# ADC_channel.net
KiCad netlist of a schematic drawn in Altium Designer
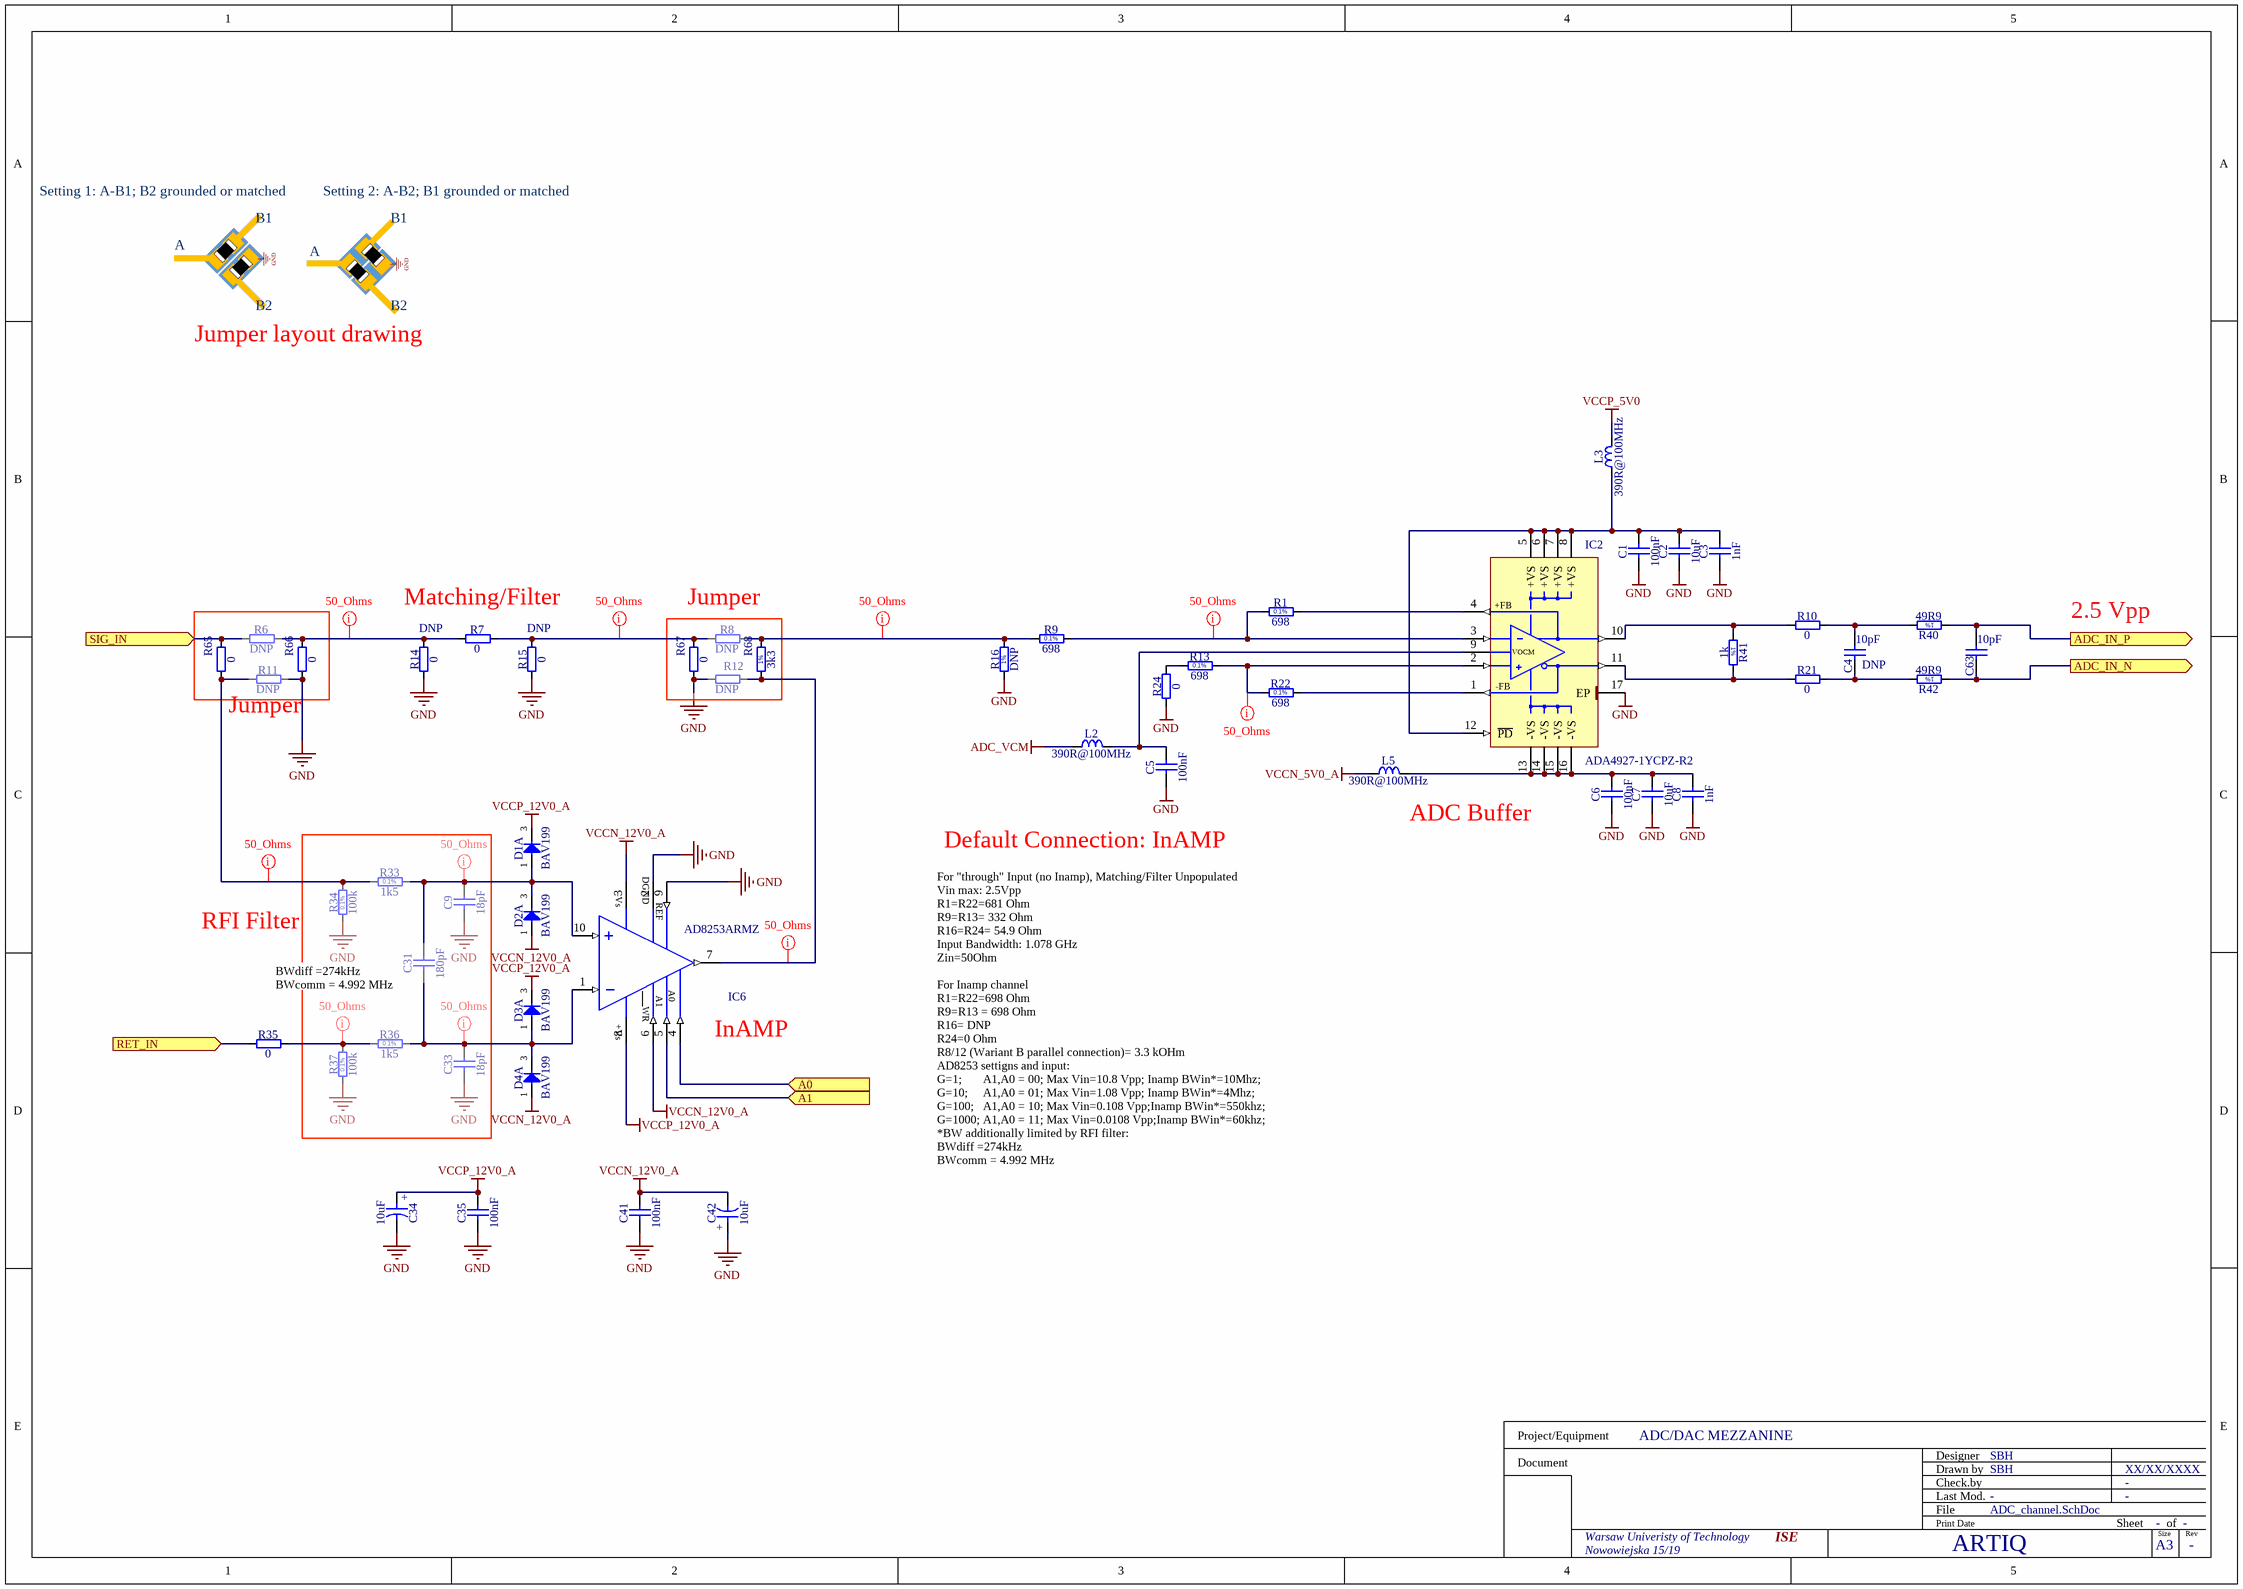
[diagram p0: ADC_channel.SchDoc]

(export (version "E")
  (design (tool "Eeschema 10.0.6"))
  (components
    (comp (ref "C1")
      (value "100nF")
      (footprint "CAPC1005X55N")
      (description "Non-polarised capacitor")
      (fields
        (field (name "PART NUMBER") "CC0402_100NF_16V_10%_X5R")
        (field (name "VOLTAGE") "16V")
        (field (name "AUTHOR") "CERN DEM JLC")
      )
      (libsource (lib "Capacitors") (part "Capacitor - non polarized"))
    )
    (comp (ref "C2")
      (value "10uF")
      (footprint "CAPC1608X87N")
      (description "Non-polarised capacitor")
      (fields
        (field (name "PART NUMBER") "CC0603_10UF_6.3V_20%_X5R")
        (field (name "VOLTAGE") "6.3V")
        (field (name "AUTHOR") "CERN DEM JLC")
      )
      (libsource (lib "Capacitors") (part "Capacitor - non polarized"))
    )
    (comp (ref "C3")
      (value "1nF")
      (footprint "CAPC1005X55N")
      (description "Non-polarised capacitor")
      (fields
        (field (name "PART NUMBER") "CC0402_1NF_50V_10%_X7R")
        (field (name "VOLTAGE") "50V")
        (field (name "AUTHOR") "CERN DEM JLC")
      )
      (libsource (lib "Capacitors") (part "Capacitor - non polarized"))
    )
    (comp (ref "C4")
      (value "10pF")
      (footprint "CAPC1608X87N")
      (description "Non-polarised capacitor")
      (fields
        (field (name "PART NUMBER") "CC0603_10PF_50V_5%_NP0")
        (field (name "VOLTAGE") "50V")
        (field (name "MOUNTED") "DNP")
        (field (name "AUTHOR") "CERN DEM JLC")
      )
      (libsource (lib "Capacitors") (part "Capacitor - non polarized"))
    )
    (comp (ref "C5")
      (value "100nF")
      (footprint "CAPC1005X55N")
      (description "Non-polarised capacitor")
      (fields
        (field (name "PART NUMBER") "CC0402_100NF_16V_10%_X5R")
        (field (name "VOLTAGE") "16V")
        (field (name "AUTHOR") "CERN DEM JLC")
      )
      (libsource (lib "Capacitors") (part "Capacitor - non polarized"))
    )
    (comp (ref "C6")
      (value "100nF")
      (footprint "CAPC1005X55N")
      (description "Non-polarised capacitor")
      (fields
        (field (name "PART NUMBER") "CC0402_100NF_16V_10%_X5R")
        (field (name "VOLTAGE") "16V")
        (field (name "AUTHOR") "CERN DEM JLC")
      )
      (libsource (lib "Capacitors") (part "Capacitor - non polarized"))
    )
    (comp (ref "C7")
      (value "10uF")
      (footprint "CAPC1608X87N")
      (description "Non-polarised capacitor")
      (fields
        (field (name "PART NUMBER") "CC0603_10UF_6.3V_20%_X5R")
        (field (name "VOLTAGE") "6.3V")
        (field (name "AUTHOR") "CERN DEM JLC")
      )
      (libsource (lib "Capacitors") (part "Capacitor - non polarized"))
    )
    (comp (ref "C8")
      (value "1nF")
      (footprint "CAPC1005X55N")
      (description "Non-polarised capacitor")
      (fields
        (field (name "PART NUMBER") "CC0402_1NF_50V_10%_X7R")
        (field (name "VOLTAGE") "50V")
        (field (name "AUTHOR") "CERN DEM JLC")
      )
      (libsource (lib "Capacitors") (part "Capacitor - non polarized"))
    )
    (comp (ref "C9")
      (value "18pF")
      (footprint "CAPC1005X55N")
      (description "Non-polarised capacitor")
      (fields
        (field (name "PART NUMBER") "CC0402_18PF_50V_5%_C0G")
        (field (name "VOLTAGE") "50V")
        (field (name "AUTHOR") "CERN DEM JLC")
      )
      (libsource (lib "Capacitors") (part "Capacitor - non polarized"))
    )
    (comp (ref "C31")
      (value "180pF")
      (footprint "CAPC3216X140N")
      (description "Non-polarised capacitor")
      (fields
        (field (name "PART NUMBER") "CC1206_180PF_50V_5%_NP0")
        (field (name "VOLTAGE") "50V")
        (field (name "AUTHOR") "CERN DEM JLC")
      )
      (libsource (lib "Capacitors") (part "Capacitor - non polarized"))
    )
    (comp (ref "C33")
      (value "18pF")
      (footprint "CAPC1005X55N")
      (description "Non-polarised capacitor")
      (fields
        (field (name "PART NUMBER") "CC0402_18PF_50V_5%_C0G")
        (field (name "VOLTAGE") "50V")
        (field (name "AUTHOR") "CERN DEM JLC")
      )
      (libsource (lib "Capacitors") (part "Capacitor - non polarized"))
    )
    (comp (ref "C34")
      (value "10uF")
      (footprint "CAPMP3216X180N")
      (description "Polarised capacitor")
      (fields
        (field (name "PART NUMBER") "CTE3216-18_10UF_16V_20%_AVX_TCJ")
        (field (name "VOLTAGE") "16V")
        (field (name "AUTHOR") "CERN DEM JLC")
      )
      (libsource (lib "Capacitors") (part "Capacitor - polarized"))
    )
    (comp (ref "C35")
      (value "100nF")
      (footprint "CAPC1005X55N")
      (description "Non-polarised capacitor")
      (fields
        (field (name "PART NUMBER") "CC0402_100NF_16V_10%_X7R")
        (field (name "VOLTAGE") "16V")
        (field (name "AUTHOR") "CERN DEM JLC")
      )
      (libsource (lib "Capacitors") (part "Capacitor - non polarized"))
    )
    (comp (ref "C41")
      (value "100nF")
      (footprint "CAPC1005X55N")
      (description "Non-polarised capacitor")
      (fields
        (field (name "PART NUMBER") "CC0402_100NF_16V_10%_X7R")
        (field (name "VOLTAGE") "16V")
        (field (name "AUTHOR") "CERN DEM JLC")
      )
      (libsource (lib "Capacitors") (part "Capacitor - non polarized"))
    )
    (comp (ref "C42")
      (value "10uF")
      (footprint "CAPMP3216X180N")
      (description "Polarised capacitor")
      (fields
        (field (name "PART NUMBER") "CTE3216-18_10UF_16V_20%_AVX_TCJ")
        (field (name "VOLTAGE") "16V")
        (field (name "AUTHOR") "CERN DEM JLC")
      )
      (libsource (lib "Capacitors") (part "Capacitor - polarized"))
    )
    (comp (ref "C63")
      (value "10pF")
      (footprint "CAPC1608X87N")
      (description "Non-polarised capacitor")
      (fields
        (field (name "PART NUMBER") "CC0603_10PF_50V_5%_NP0")
        (field (name "VOLTAGE") "50V")
        (field (name "AUTHOR") "CERN DEM JLC")
      )
      (libsource (lib "Capacitors") (part "Capacitor - non polarized"))
    )
    (comp (ref "D1")
      (value "BAV199")
      (footprint "SOT95P240X110-3N")
      (description "Serial Diode")
      (fields
        (field (name "VOLTAGE") "75V")
        (field (name "POWER") "250mW")
        (field (name "AUTHOR") "CERN DEM JMW")
      )
      (libsource (lib "ICs And Semiconductors") (part "Diode x2 A1C3_A3C2"))
    )
    (comp (ref "D2")
      (value "BAV199")
      (footprint "SOT95P240X110-3N")
      (description "Serial Diode")
      (fields
        (field (name "VOLTAGE") "75V")
        (field (name "POWER") "250mW")
        (field (name "AUTHOR") "CERN DEM JMW")
      )
      (libsource (lib "ICs And Semiconductors") (part "Diode x2 A1C3_A3C2"))
    )
    (comp (ref "D3")
      (value "BAV199")
      (footprint "SOT95P240X110-3N")
      (description "Serial Diode")
      (fields
        (field (name "VOLTAGE") "75V")
        (field (name "POWER") "250mW")
        (field (name "AUTHOR") "CERN DEM JMW")
      )
      (libsource (lib "ICs And Semiconductors") (part "Diode x2 A1C3_A3C2"))
    )
    (comp (ref "D4")
      (value "BAV199")
      (footprint "SOT95P240X110-3N")
      (description "Serial Diode")
      (fields
        (field (name "VOLTAGE") "75V")
        (field (name "POWER") "250mW")
        (field (name "AUTHOR") "CERN DEM JMW")
      )
      (libsource (lib "ICs And Semiconductors") (part "Diode x2 A1C3_A3C2"))
    )
    (comp (ref "IC2")
      (value "ADA4927-1YCPZ-R2")
      (footprint "QFN50P300X300X100-17N-S145")
      (description "Ultralow Distortion Current Feedback Differential ADC Driver")
      (fields (field (name "MANUFACTURER") "ANALOG DEVICES") (field (name "AUTHOR") "CERN DEM JLC"))
      (libsource (lib "ICs And Semiconductors") (part "ADA4927-1"))
    )
    (comp (ref "IC6")
      (value "AD8253ARMZ")
      (footprint "SOP50P490X110-10N")
      (description "10MHz, 20V/us, G= 1, 10, 100, 1000 iCMOS Programmable Gain Instrumentation Amplifier")
      (fields (field (name "MANUFACTURER") "ANALOG DEVICES") (field (name "AUTHOR") "CERN DEM JLC"))
      (libsource (lib "ICs And Semiconductors") (part "AD8253"))
    )
    (comp (ref "L2")
      (value "390R@100MHz")
      (footprint "INDC1608X95N")
      (description "Inductor")
      (fields
        (field (name "PART NUMBER") "IND0603_TDK_MPZ1608R391A")
        (field (name "POWER") "1.2A")
        (field (name "AUTHOR") "CERN DEM JLC")
      )
      (libsource (lib "Inductors & Transformers") (part "Inductor"))
    )
    (comp (ref "L3")
      (value "390R@100MHz")
      (footprint "INDC1608X95N")
      (description "Inductor")
      (fields
        (field (name "PART NUMBER") "IND0603_TDK_MPZ1608R391A")
        (field (name "POWER") "1.2A")
        (field (name "AUTHOR") "CERN DEM JLC")
      )
      (libsource (lib "") (part "Inductor_1"))
    )
    (comp (ref "L5")
      (value "390R@100MHz")
      (footprint "INDC1608X95N")
      (description "Inductor")
      (fields
        (field (name "PART NUMBER") "IND0603_TDK_MPZ1608R391A")
        (field (name "POWER") "1.2A")
        (field (name "AUTHOR") "CERN DEM JLC")
      )
      (libsource (lib "Inductors & Transformers") (part "Inductor"))
    )
    (comp (ref "R1")
      (value "698")
      (footprint "RESC1608X55N")
      (description "Resistor - 0.1%")
      (fields
        (field (name "PART NUMBER") "R0603_698R_0.1%_0.063W_10PPM")
        (field (name "POWER") "0.063W")
        (field (name "AUTHOR") "CERN DEM JLC")
      )
      (libsource (lib "Resistors") (part "Resistor - 0.1%"))
    )
    (comp (ref "R6")
      (value "DNP")
      (footprint "RESC1005X40N")
      (description "Resistor")
      (fields
        (field (name "PART NUMBER") "R0402_0R_JUMPER")
        (field (name "MANUFACTURER") "GENERIC")
        (field (name "AUTHOR") "CERN DEM JLC")
      )
      (libsource (lib "Resistors") (part "Resistor"))
    )
    (comp (ref "R7")
      (value "0")
      (footprint "RESC1005X40N")
      (description "Resistor")
      (fields
        (field (name "PART NUMBER") "R0402_0R_JUMPER")
        (field (name "MANUFACTURER") "GENERIC")
        (field (name "AUTHOR") "CERN DEM JLC")
      )
      (libsource (lib "Resistors") (part "Resistor"))
    )
    (comp (ref "R8")
      (value "DNP")
      (footprint "RESC1005X40N")
      (description "Resistor")
      (fields
        (field (name "PART NUMBER") "R0402_0R_JUMPER")
        (field (name "MANUFACTURER") "GENERIC")
        (field (name "AUTHOR") "CERN DEM JLC")
      )
      (libsource (lib "Resistors") (part "Resistor"))
    )
    (comp (ref "R9")
      (value "698")
      (footprint "RESC1608X55N")
      (description "Resistor - 0.1%")
      (fields
        (field (name "PART NUMBER") "R0603_698R_0.1%_0.063W_10PPM")
        (field (name "POWER") "0.063W")
        (field (name "AUTHOR") "CERN DEM JLC")
      )
      (libsource (lib "Resistors") (part "Resistor - 0.1%"))
    )
    (comp (ref "R10")
      (value "0")
      (footprint "RESC1005X40N")
      (description "Resistor")
      (fields
        (field (name "PART NUMBER") "R0402_0R_JUMPER")
        (field (name "MANUFACTURER") "GENERIC")
        (field (name "AUTHOR") "CERN DEM JLC")
      )
      (libsource (lib "Resistors") (part "Resistor"))
    )
    (comp (ref "R11")
      (value "DNP")
      (footprint "RESC1005X40N")
      (description "Resistor")
      (fields
        (field (name "PART NUMBER") "R0402_0R_JUMPER")
        (field (name "MANUFACTURER") "GENERIC")
        (field (name "AUTHOR") "CERN DEM JLC")
      )
      (libsource (lib "Resistors") (part "Resistor"))
    )
    (comp (ref "R12")
      (value "DNP")
      (footprint "RESC1005X40N")
      (description "Resistor")
      (fields
        (field (name "PART NUMBER") "R0402_0R_JUMPER")
        (field (name "MANUFACTURER") "GENERIC")
        (field (name "AUTHOR") "CERN DEM JLC")
      )
      (libsource (lib "Resistors") (part "Resistor"))
    )
    (comp (ref "R13")
      (value "698")
      (footprint "RESC1608X55N")
      (description "Resistor - 0.1%")
      (fields
        (field (name "PART NUMBER") "R0603_698R_0.1%_0.063W_10PPM")
        (field (name "POWER") "0.063W")
        (field (name "AUTHOR") "CERN DEM JLC")
      )
      (libsource (lib "Resistors") (part "Resistor - 0.1%"))
    )
    (comp (ref "R14")
      (value "0")
      (footprint "RESC1005X40N")
      (description "Resistor")
      (fields
        (field (name "PART NUMBER") "R0402_0R_JUMPER")
        (field (name "MANUFACTURER") "GENERIC")
        (field (name "MOUNTED") "DNP")
        (field (name "AUTHOR") "CERN DEM JLC")
      )
      (libsource (lib "Resistors") (part "Resistor"))
    )
    (comp (ref "R15")
      (value "0")
      (footprint "RESC1005X40N")
      (description "Resistor")
      (fields
        (field (name "PART NUMBER") "R0402_0R_JUMPER")
        (field (name "MANUFACTURER") "GENERIC")
        (field (name "MOUNTED") "DNP")
        (field (name "AUTHOR") "CERN DEM JLC")
      )
      (libsource (lib "Resistors") (part "Resistor"))
    )
    (comp (ref "R16")
      (value "DNP")
      (footprint "RESC1005X40N")
      (description "Resistor - 1%")
      (fields
        (field (name "PART NUMBER") "R0402_56R_1%_0.0625W_100PPM")
        (field (name "POWER") "0.0625W")
        (field (name "AUTHOR") "CERN DEM JLC")
      )
      (libsource (lib "Resistors") (part "Resistor - 1%"))
    )
    (comp (ref "R21")
      (value "0")
      (footprint "RESC1005X40N")
      (description "Resistor")
      (fields
        (field (name "PART NUMBER") "R0402_0R_JUMPER")
        (field (name "MANUFACTURER") "GENERIC")
        (field (name "AUTHOR") "CERN DEM JLC")
      )
      (libsource (lib "Resistors") (part "Resistor"))
    )
    (comp (ref "R22")
      (value "698")
      (footprint "RESC1608X55N")
      (description "Resistor - 0.1%")
      (fields
        (field (name "PART NUMBER") "R0603_698R_0.1%_0.063W_10PPM")
        (field (name "POWER") "0.063W")
        (field (name "AUTHOR") "CERN DEM JLC")
      )
      (libsource (lib "Resistors") (part "Resistor - 0.1%"))
    )
    (comp (ref "R24")
      (value "0")
      (footprint "RESC1005X40N")
      (description "Resistor")
      (fields
        (field (name "PART NUMBER") "R0402_0R_JUMPER")
        (field (name "MANUFACTURER") "GENERIC")
        (field (name "AUTHOR") "CERN DEM JLC")
      )
      (libsource (lib "Resistors") (part "Resistor"))
    )
    (comp (ref "R33")
      (value "1k5")
      (footprint "RESC1608X55N")
      (description "Resistor - 0.1%")
      (fields
        (field (name "PART NUMBER") "R0603_1K5_0.1%_0.063W_10PPM")
        (field (name "POWER") "0.063W")
        (field (name "AUTHOR") "CERN DEM JLC")
      )
      (libsource (lib "Resistors") (part "Resistor - 0.1%"))
    )
    (comp (ref "R34")
      (value "100k")
      (footprint "RESC1005X35N")
      (description "Resistor - 0.1%")
      (fields
        (field (name "PART NUMBER") "R0402_100K_0.1%_0.063W_25PPM")
        (field (name "POWER") "0.063W")
        (field (name "AUTHOR") "CERN DEM JMW")
      )
      (libsource (lib "Resistors") (part "Resistor - 0.1%"))
    )
    (comp (ref "R35")
      (value "0")
      (footprint "RESC1005X40N")
      (description "Resistor")
      (fields
        (field (name "PART NUMBER") "R0402_0R_JUMPER")
        (field (name "MANUFACTURER") "GENERIC")
        (field (name "AUTHOR") "CERN DEM JLC")
      )
      (libsource (lib "Resistors") (part "Resistor"))
    )
    (comp (ref "R36")
      (value "1k5")
      (footprint "RESC1608X55N")
      (description "Resistor - 0.1%")
      (fields
        (field (name "PART NUMBER") "R0603_1K5_0.1%_0.063W_10PPM")
        (field (name "POWER") "0.063W")
        (field (name "AUTHOR") "CERN DEM JLC")
      )
      (libsource (lib "Resistors") (part "Resistor - 0.1%"))
    )
    (comp (ref "R37")
      (value "100k")
      (footprint "RESC1005X35N")
      (description "Resistor - 0.1%")
      (fields
        (field (name "PART NUMBER") "R0402_100K_0.1%_0.063W_25PPM")
        (field (name "POWER") "0.063W")
        (field (name "AUTHOR") "CERN DEM JMW")
      )
      (libsource (lib "Resistors") (part "Resistor - 0.1%"))
    )
    (comp (ref "R40")
      (value "49R9")
      (footprint "RESC1005X40N")
      (description "Resistor - 1%")
      (fields
        (field (name "PART NUMBER") "R0402_49R9_1%_0.0625W_100PPM")
        (field (name "POWER") "0.0625W")
        (field (name "AUTHOR") "CERN DEM JLC")
      )
      (libsource (lib "Resistors") (part "Resistor - 1%"))
    )
    (comp (ref "R41")
      (value "1k")
      (footprint "RESC1005X40N")
      (description "Resistor - 1%")
      (fields
        (field (name "PART NUMBER") "R0402_1K_1%_0.0625W_100PPM")
        (field (name "POWER") "0.0625W")
        (field (name "AUTHOR") "CERN DEM JLC")
      )
      (libsource (lib "Resistors") (part "Resistor - 1%"))
    )
    (comp (ref "R42")
      (value "49R9")
      (footprint "RESC1005X40N")
      (description "Resistor - 1%")
      (fields
        (field (name "PART NUMBER") "R0402_49R9_1%_0.0625W_100PPM")
        (field (name "POWER") "0.0625W")
        (field (name "AUTHOR") "CERN DEM JLC")
      )
      (libsource (lib "Resistors") (part "Resistor - 1%"))
    )
    (comp (ref "R65")
      (value "0")
      (footprint "RESC1005X40N")
      (description "Resistor")
      (fields
        (field (name "PART NUMBER") "R0402_0R_JUMPER")
        (field (name "MANUFACTURER") "GENERIC")
        (field (name "AUTHOR") "CERN DEM JLC")
      )
      (libsource (lib "Resistors") (part "Resistor"))
    )
    (comp (ref "R66")
      (value "0")
      (footprint "RESC1005X40N")
      (description "Resistor")
      (fields
        (field (name "PART NUMBER") "R0402_0R_JUMPER")
        (field (name "MANUFACTURER") "GENERIC")
        (field (name "AUTHOR") "CERN DEM JLC")
      )
      (libsource (lib "Resistors") (part "Resistor"))
    )
    (comp (ref "R67")
      (value "0")
      (footprint "RESC1005X40N")
      (description "Resistor")
      (fields
        (field (name "PART NUMBER") "R0402_0R_JUMPER")
        (field (name "MANUFACTURER") "GENERIC")
        (field (name "AUTHOR") "CERN DEM JLC")
      )
      (libsource (lib "Resistors") (part "Resistor"))
    )
    (comp (ref "R68")
      (value "3k3")
      (footprint "RESC1005X40N")
      (description "Resistor - 1%")
      (fields
        (field (name "PART NUMBER") "R0402_3K3_1%_0.0625W_100PPM")
        (field (name "MANUFACTURER") "GENERIC")
        (field (name "AUTHOR") "CERN DEM JLC")
      )
      (libsource (lib "Resistors") (part "Resistor - 1%"))
    )
  )
  (nets
    (net (code "1") (name "/A0") (class "Default")
      (node (ref "IC6") (pin "4") (pinfunction "A0_4") (pintype "input"))
    )
    (net (code "2") (name "/A1") (class "Default")
      (node (ref "IC6") (pin "5") (pinfunction "A1_5") (pintype "input"))
    )
    (net (code "3") (name "/ADC_IN_N") (class "Default")
      (node (ref "C63") (pin "1") (pinfunction "1_1") (pintype "passive"))
      (node (ref "R42") (pin "1") (pinfunction "1_1") (pintype "passive"))
    )
    (net (code "4") (name "/ADC_IN_P") (class "Default")
      (node (ref "C63") (pin "2") (pinfunction "2_2") (pintype "passive"))
      (node (ref "R40") (pin "1") (pinfunction "1_1") (pintype "passive"))
    )
    (net (code "5") (name "/RET_IN") (class "Default")
      (node (ref "R35") (pin "1") (pinfunction "1_1") (pintype "passive"))
    )
    (net (code "6") (name "/SIG_IN") (class "Default")
      (node (ref "R6") (pin "1") (pinfunction "1_1") (pintype "passive"))
      (node (ref "R65") (pin "2") (pinfunction "2_2") (pintype "passive"))
    )
    (net (code "7") (name "ADC_VCM") (class "Default")
      (node (ref "L2") (pin "1") (pinfunction "1_1") (pintype "passive"))
    )
    (net (code "8") (name "GND") (class "Default")
      (node (ref "C1") (pin "1") (pinfunction "1_1") (pintype "passive"))
      (node (ref "C2") (pin "1") (pinfunction "1_1") (pintype "passive"))
      (node (ref "C3") (pin "1") (pinfunction "1_1") (pintype "passive"))
      (node (ref "C33") (pin "1") (pinfunction "1_1") (pintype "passive"))
      (node (ref "C34") (pin "2") (pinfunction "2_2") (pintype "passive"))
      (node (ref "C35") (pin "1") (pinfunction "1_1") (pintype "passive"))
      (node (ref "C41") (pin "1") (pinfunction "1_1") (pintype "passive"))
      (node (ref "C42") (pin "1") (pinfunction "1_1") (pintype "passive"))
      (node (ref "C5") (pin "1") (pinfunction "1_1") (pintype "passive"))
      (node (ref "C6") (pin "1") (pinfunction "1_1") (pintype "passive"))
      (node (ref "C7") (pin "1") (pinfunction "1_1") (pintype "passive"))
      (node (ref "C8") (pin "1") (pinfunction "1_1") (pintype "passive"))
      (node (ref "C9") (pin "1") (pinfunction "1_1") (pintype "passive"))
      (node (ref "IC2") (pin "17") (pinfunction "EP_17") (pintype "power_in"))
      (node (ref "IC6") (pin "2") (pinfunction "DGND_2") (pintype "power_in"))
      (node (ref "IC6") (pin "9") (pinfunction "REF_9") (pintype "input"))
      (node (ref "R11") (pin "2") (pinfunction "2_2") (pintype "passive"))
      (node (ref "R12") (pin "2") (pinfunction "2_2") (pintype "passive"))
      (node (ref "R14") (pin "1") (pinfunction "1_1") (pintype "passive"))
      (node (ref "R15") (pin "1") (pinfunction "1_1") (pintype "passive"))
      (node (ref "R16") (pin "1") (pinfunction "1_1") (pintype "passive"))
      (node (ref "R24") (pin "1") (pinfunction "1_1") (pintype "passive"))
      (node (ref "R34") (pin "1") (pinfunction "1_1") (pintype "passive"))
      (node (ref "R37") (pin "1") (pinfunction "1_1") (pintype "passive"))
      (node (ref "R66") (pin "1") (pinfunction "1_1") (pintype "passive"))
      (node (ref "R67") (pin "1") (pinfunction "1_1") (pintype "passive"))
    )
    (net (code "9") (name "Net-(C4-Pad1)") (class "Default")
      (node (ref "C4") (pin "1") (pinfunction "1_1") (pintype "passive"))
      (node (ref "R21") (pin "2") (pinfunction "2_2") (pintype "passive"))
      (node (ref "R42") (pin "2") (pinfunction "2_2") (pintype "passive"))
    )
    (net (code "10") (name "Net-(C4-Pad2)") (class "Default")
      (node (ref "C4") (pin "2") (pinfunction "2_2") (pintype "passive"))
      (node (ref "R10") (pin "2") (pinfunction "2_2") (pintype "passive"))
      (node (ref "R40") (pin "2") (pinfunction "2_2") (pintype "passive"))
    )
    (net (code "11") (name "Net-(C6-Pad2)") (class "Default")
      (node (ref "C6") (pin "2") (pinfunction "2_2") (pintype "passive"))
      (node (ref "C7") (pin "2") (pinfunction "2_2") (pintype "passive"))
      (node (ref "C8") (pin "2") (pinfunction "2_2") (pintype "passive"))
      (node (ref "IC2") (pin "13") (pinfunction "-VS_13") (pintype "power_in"))
      (node (ref "IC2") (pin "14") (pinfunction "-VS_14") (pintype "power_in"))
      (node (ref "IC2") (pin "15") (pinfunction "-VS_15") (pintype "power_in"))
      (node (ref "IC2") (pin "16") (pinfunction "-VS_16") (pintype "power_in"))
      (node (ref "L5") (pin "2") (pinfunction "2_2") (pintype "passive"))
    )
    (net (code "12") (name "Net-(D1A-A)") (class "Default")
      (node (ref "C31") (pin "2") (pinfunction "2_2") (pintype "passive"))
      (node (ref "C9") (pin "2") (pinfunction "2_2") (pintype "passive"))
      (node (ref "D1") (pin "1") (pinfunction "A_1") (pintype "passive"))
      (node (ref "D2") (pin "3") (pinfunction "COMAC_3") (pintype "passive"))
      (node (ref "IC6") (pin "10") (pinfunction "+IN_10") (pintype "input"))
      (node (ref "R33") (pin "2") (pinfunction "2_2") (pintype "passive"))
    )
    (net (code "13") (name "Net-(D3A-A)") (class "Default")
      (node (ref "C31") (pin "1") (pinfunction "1_1") (pintype "passive"))
      (node (ref "C33") (pin "2") (pinfunction "2_2") (pintype "passive"))
      (node (ref "D3") (pin "1") (pinfunction "A_1") (pintype "passive"))
      (node (ref "D4") (pin "3") (pinfunction "COMAC_3") (pintype "passive"))
      (node (ref "IC6") (pin "1") (pinfunction "-IN_1") (pintype "input"))
      (node (ref "R36") (pin "2") (pinfunction "2_2") (pintype "passive"))
    )
    (net (code "14") (name "Net-(IC2-+FB)") (class "Default")
      (node (ref "IC2") (pin "4") (pinfunction "+FB_4") (pintype "output"))
      (node (ref "R1") (pin "2") (pinfunction "2_2") (pintype "passive"))
    )
    (net (code "15") (name "Net-(IC2-+IN)") (class "Default")
      (node (ref "IC2") (pin "2") (pinfunction "+IN_2") (pintype "input"))
      (node (ref "R13") (pin "2") (pinfunction "2_2") (pintype "passive"))
      (node (ref "R22") (pin "1") (pinfunction "1_1") (pintype "passive"))
    )
    (net (code "16") (name "Net-(IC2-+OUT)") (class "Default")
      (node (ref "IC2") (pin "10") (pinfunction "+OUT_10") (pintype "output"))
      (node (ref "R10") (pin "1") (pinfunction "1_1") (pintype "passive"))
      (node (ref "R41") (pin "1") (pinfunction "1_1") (pintype "passive"))
    )
    (net (code "17") (name "Net-(IC2--FB)") (class "Default")
      (node (ref "IC2") (pin "1") (pinfunction "-FB_1") (pintype "output"))
      (node (ref "R22") (pin "2") (pinfunction "2_2") (pintype "passive"))
    )
    (net (code "18") (name "Net-(IC2--IN)") (class "Default")
      (node (ref "IC2") (pin "3") (pinfunction "-IN_3") (pintype "input"))
      (node (ref "R1") (pin "1") (pinfunction "1_1") (pintype "passive"))
      (node (ref "R9") (pin "2") (pinfunction "2_2") (pintype "passive"))
    )
    (net (code "19") (name "Net-(IC2--OUT)") (class "Default")
      (node (ref "IC2") (pin "11") (pinfunction "-OUT_11") (pintype "output"))
      (node (ref "R21") (pin "1") (pinfunction "1_1") (pintype "passive"))
      (node (ref "R41") (pin "2") (pinfunction "2_2") (pintype "passive"))
    )
    (net (code "20") (name "Net-(IC2-VOCM)") (class "Default")
      (node (ref "C5") (pin "2") (pinfunction "2_2") (pintype "passive"))
      (node (ref "IC2") (pin "9") (pinfunction "VOCM_9") (pintype "passive"))
      (node (ref "L2") (pin "2") (pinfunction "2_2") (pintype "passive"))
    )
    (net (code "21") (name "Net-(IC2-~{PD})") (class "Default")
      (node (ref "C1") (pin "2") (pinfunction "2_2") (pintype "passive"))
      (node (ref "C2") (pin "2") (pinfunction "2_2") (pintype "passive"))
      (node (ref "C3") (pin "2") (pinfunction "2_2") (pintype "passive"))
      (node (ref "IC2") (pin "12") (pinfunction "~{PD}_12") (pintype "input"))
      (node (ref "IC2") (pin "5") (pinfunction "+VS_5") (pintype "power_in"))
      (node (ref "IC2") (pin "6") (pinfunction "+VS_6") (pintype "power_in"))
      (node (ref "IC2") (pin "7") (pinfunction "+VS_7") (pintype "power_in"))
      (node (ref "IC2") (pin "8") (pinfunction "+VS_8") (pintype "power_in"))
      (node (ref "L3") (pin "1") (pinfunction "1_1") (pintype "passive"))
    )
    (net (code "22") (name "Net-(IC6-OUT)") (class "Default")
      (node (ref "IC6") (pin "7") (pinfunction "OUT_7") (pintype "output"))
      (node (ref "R12") (pin "1") (pinfunction "1_1") (pintype "passive"))
      (node (ref "R68") (pin "1") (pinfunction "1_1") (pintype "passive"))
    )
    (net (code "23") (name "Net-(R11-Pad1)") (class "Default")
      (node (ref "R11") (pin "1") (pinfunction "1_1") (pintype "passive"))
      (node (ref "R33") (pin "1") (pinfunction "1_1") (pintype "passive"))
      (node (ref "R34") (pin "2") (pinfunction "2_2") (pintype "passive"))
      (node (ref "R65") (pin "1") (pinfunction "1_1") (pintype "passive"))
    )
    (net (code "24") (name "Net-(R13-Pad1)") (class "Default")
      (node (ref "R13") (pin "1") (pinfunction "1_1") (pintype "passive"))
      (node (ref "R24") (pin "2") (pinfunction "2_2") (pintype "passive"))
    )
    (net (code "25") (name "Net-(R14-Pad2)") (class "Default")
      (node (ref "R14") (pin "2") (pinfunction "2_2") (pintype "passive"))
      (node (ref "R6") (pin "2") (pinfunction "2_2") (pintype "passive"))
      (node (ref "R66") (pin "2") (pinfunction "2_2") (pintype "passive"))
      (node (ref "R7") (pin "1") (pinfunction "1_1") (pintype "passive"))
    )
    (net (code "26") (name "Net-(R15-Pad2)") (class "Default")
      (node (ref "R15") (pin "2") (pinfunction "2_2") (pintype "passive"))
      (node (ref "R67") (pin "2") (pinfunction "2_2") (pintype "passive"))
      (node (ref "R7") (pin "2") (pinfunction "2_2") (pintype "passive"))
      (node (ref "R8") (pin "2") (pinfunction "2_2") (pintype "passive"))
    )
    (net (code "27") (name "Net-(R16-Pad2)") (class "Default")
      (node (ref "R16") (pin "2") (pinfunction "2_2") (pintype "passive"))
      (node (ref "R68") (pin "2") (pinfunction "2_2") (pintype "passive"))
      (node (ref "R8") (pin "1") (pinfunction "1_1") (pintype "passive"))
      (node (ref "R9") (pin "1") (pinfunction "1_1") (pintype "passive"))
    )
    (net (code "28") (name "Net-(R35-Pad2)") (class "Default")
      (node (ref "R35") (pin "2") (pinfunction "2_2") (pintype "passive"))
      (node (ref "R36") (pin "1") (pinfunction "1_1") (pintype "passive"))
      (node (ref "R37") (pin "2") (pinfunction "2_2") (pintype "passive"))
    )
    (net (code "29") (name "VCCN_5V0_A") (class "Default")
      (node (ref "L5") (pin "1") (pinfunction "1_1") (pintype "passive"))
    )
    (net (code "30") (name "VCCN_12V0_A") (class "Default")
      (node (ref "C41") (pin "2") (pinfunction "2_2") (pintype "passive"))
      (node (ref "C42") (pin "2") (pinfunction "2_2") (pintype "passive"))
      (node (ref "D2") (pin "1") (pinfunction "A_1") (pintype "passive"))
      (node (ref "D4") (pin "1") (pinfunction "A_1") (pintype "passive"))
      (node (ref "IC6") (pin "3") (pinfunction "-VS_3") (pintype "power_in"))
      (node (ref "IC6") (pin "6") (pinfunction "~{WR}_6") (pintype "input"))
    )
    (net (code "31") (name "VCCP_5V0") (class "Default")
      (node (ref "L3") (pin "2") (pinfunction "2_2") (pintype "passive"))
    )
    (net (code "32") (name "VCCP_12V0_A") (class "Default")
      (node (ref "C34") (pin "1") (pinfunction "1_1") (pintype "passive"))
      (node (ref "C35") (pin "2") (pinfunction "2_2") (pintype "passive"))
      (node (ref "D1") (pin "3") (pinfunction "COMAC_3") (pintype "passive"))
      (node (ref "D3") (pin "3") (pinfunction "COMAC_3") (pintype "passive"))
      (node (ref "IC6") (pin "8") (pinfunction "+VS_8") (pintype "power_in"))
    )
  )
)
